# wiiceiver_v1.net
KiCad netlist of a schematic drawn in EAGLE
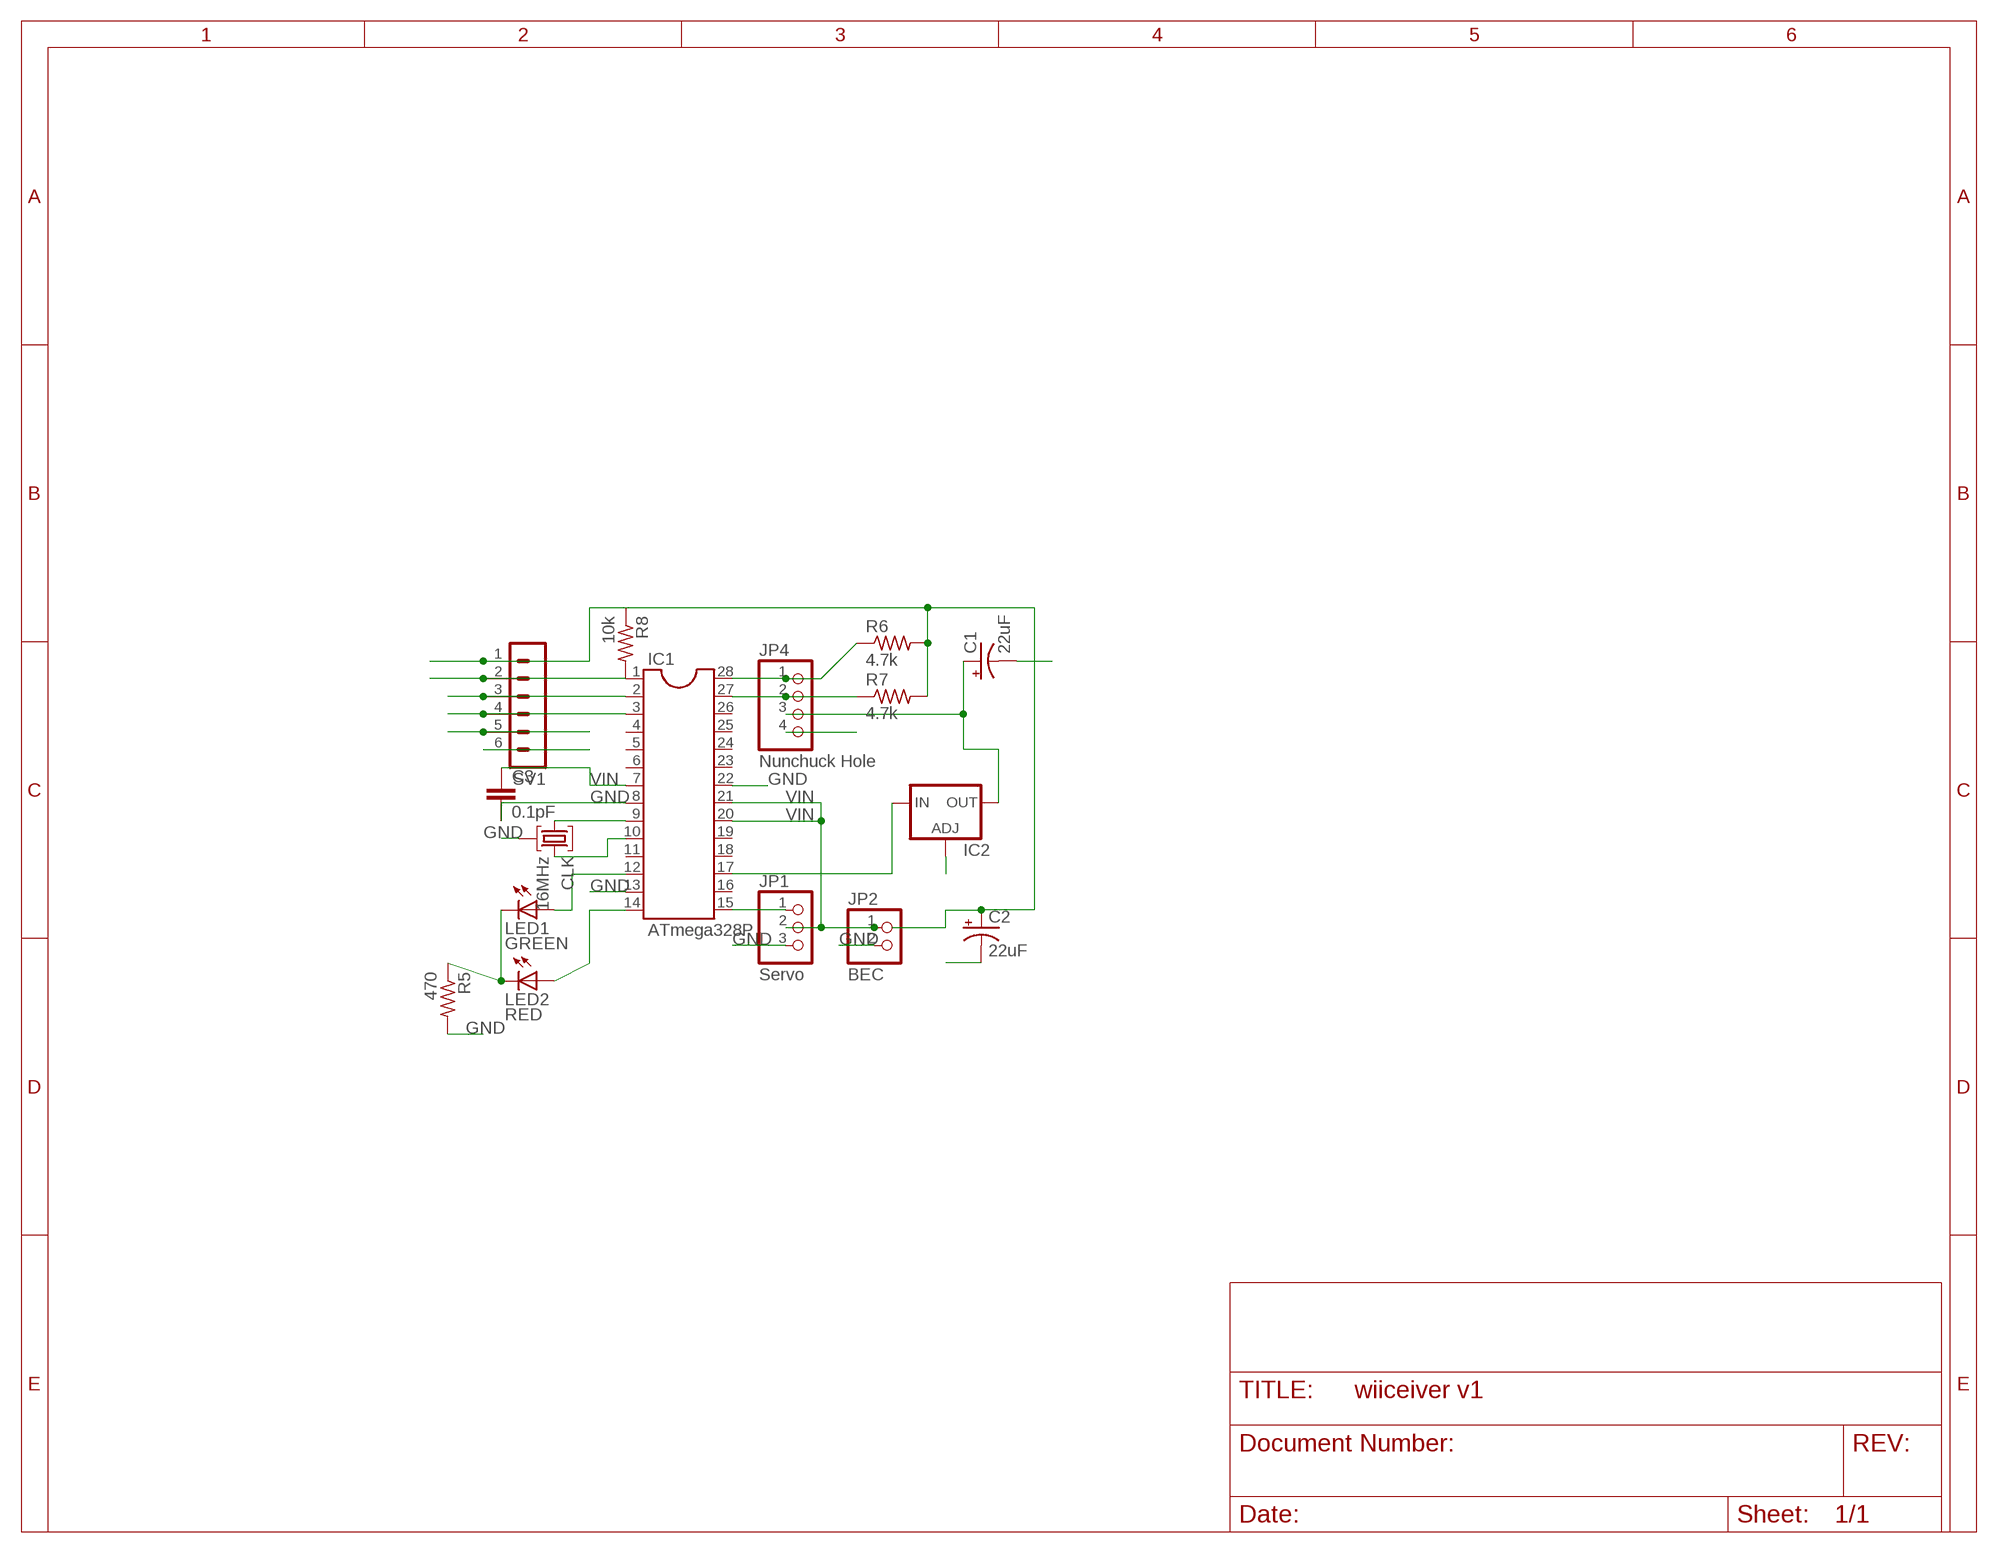
[diagram p0: schematic, sheet 1]

(export (version "E")
  (design (tool "Eeschema 10.0.6"))
  (components
    (comp (ref "C1")
      (value "22uF")
      (footprint "eagle-import:B45181A")
      (libsource (lib "eagle-import") (part "CPOL-USB45181A"))
    )
    (comp (ref "C2")
      (value "22uF")
      (footprint "eagle-import:B45181A")
      (libsource (lib "eagle-import") (part "CPOL-USB45181A"))
    )
    (comp (ref "C3")
      (value "0.1pF")
      (footprint "eagle-import:C5B2.5")
      (libsource (lib "eagle-import") (part "C5/2.5"))
    )
    (comp (ref "CLK")
      (value "16MHz")
      (footprint "eagle-import:HC49U")
      (libsource (lib "eagle-import") (part "IXFA"))
    )
    (comp (ref "IC1")
      (value "ATmega328P")
      (footprint "eagle-import:DIL28-3")
      (libsource (lib "eagle-import") (part "DIL28-3"))
    )
    (comp (ref "IC2")
      (value "LM317TS")
      (footprint "eagle-import:317TS")
      (libsource (lib "eagle-import") (part "LM317TS"))
    )
    (comp (ref "JP1")
      (value "Servo")
      (footprint "eagle-import:1X03")
      (libsource (lib "eagle-import") (part "PINHD-1X3"))
    )
    (comp (ref "JP2")
      (value "BEC")
      (footprint "eagle-import:1X02")
      (libsource (lib "eagle-import") (part "PINHD-1X2"))
    )
    (comp (ref "JP4")
      (value "Nunchuck Hole")
      (footprint "eagle-import:1X04")
      (libsource (lib "eagle-import") (part "PINHD-1X4"))
    )
    (comp (ref "LED1")
      (value "GREEN")
      (footprint "eagle-import:LED3MM")
      (libsource (lib "eagle-import") (part "LED3MM"))
    )
    (comp (ref "LED2")
      (value "RED")
      (footprint "eagle-import:LED3MM")
      (libsource (lib "eagle-import") (part "LED3MM"))
    )
    (comp (ref "R5")
      (value "470")
      (footprint "eagle-import:0204V")
      (libsource (lib "eagle-import") (part "R-US_0204/2V"))
    )
    (comp (ref "R6")
      (value "4.7k")
      (footprint "eagle-import:0204V")
      (libsource (lib "eagle-import") (part "R-US_0204/2V"))
    )
    (comp (ref "R7")
      (value "4.7k")
      (footprint "eagle-import:0204V")
      (libsource (lib "eagle-import") (part "R-US_0204/2V"))
    )
    (comp (ref "R8")
      (value "10k")
      (footprint "eagle-import:0204V")
      (libsource (lib "eagle-import") (part "R-US_0204/2V"))
    )
    (comp (ref "SV1")
      (value "MA06-1")
      (footprint "eagle-import:MA06-1")
      (libsource (lib "eagle-import") (part "MA06-1"))
    )
  )
  (nets
    (net (code "1") (name "/GND") (class "Default")
      (node (ref "C1") (pin "-") (pinfunction "-_-") (pintype "passive"))
      (node (ref "C2") (pin "-") (pinfunction "-_-") (pintype "passive"))
      (node (ref "C3") (pin "2") (pinfunction "2_2") (pintype "passive"))
      (node (ref "CLK") (pin "2") (pinfunction "2_2") (pintype "passive"))
      (node (ref "IC1") (pin "13") (pinfunction "13_13") (pintype "passive"))
      (node (ref "IC1") (pin "22") (pinfunction "22_22") (pintype "passive"))
      (node (ref "IC1") (pin "8") (pinfunction "8_8") (pintype "passive"))
      (node (ref "IC2") (pin "1") (pinfunction "ADJ_1") (pintype "input"))
      (node (ref "JP1") (pin "3") (pinfunction "3_3") (pintype "passive"))
      (node (ref "JP2") (pin "2") (pinfunction "2_2") (pintype "passive"))
      (node (ref "JP4") (pin "4") (pinfunction "4_4") (pintype "passive"))
      (node (ref "R5") (pin "2") (pinfunction "2_2") (pintype "passive"))
      (node (ref "SV1") (pin "5") (pinfunction "5_5") (pintype "passive"))
      (node (ref "SV1") (pin "6") (pinfunction "6_6") (pintype "passive"))
    )
    (net (code "2") (name "/VIN") (class "Default")
      (node (ref "C2") (pin "+") (pinfunction "+_+") (pintype "passive"))
      (node (ref "C3") (pin "1") (pinfunction "1_1") (pintype "passive"))
      (node (ref "IC1") (pin "20") (pinfunction "20_20") (pintype "passive"))
      (node (ref "IC1") (pin "21") (pinfunction "21_21") (pintype "passive"))
      (node (ref "IC1") (pin "7") (pinfunction "7_7") (pintype "passive"))
      (node (ref "JP1") (pin "2") (pinfunction "2_2") (pintype "passive"))
      (node (ref "JP2") (pin "1") (pinfunction "1_1") (pintype "passive"))
      (node (ref "R6") (pin "2") (pinfunction "2_2") (pintype "passive"))
      (node (ref "R7") (pin "2") (pinfunction "2_2") (pintype "passive"))
      (node (ref "R8") (pin "1") (pinfunction "1_1") (pintype "passive"))
      (node (ref "SV1") (pin "1") (pinfunction "1_1") (pintype "passive"))
    )
    (net (code "3") (name "Net-(CLK-Pad1)") (class "Default")
      (node (ref "CLK") (pin "1") (pinfunction "1_1") (pintype "passive"))
      (node (ref "IC1") (pin "9") (pinfunction "9_9") (pintype "passive"))
    )
    (net (code "4") (name "Net-(CLK-Pad3)") (class "Default")
      (node (ref "CLK") (pin "3") (pinfunction "3_3") (pintype "passive"))
      (node (ref "IC1") (pin "10") (pinfunction "10_10") (pintype "passive"))
    )
    (net (code "5") (name "Net-(IC1-Pad1)") (class "Default")
      (node (ref "IC1") (pin "1") (pinfunction "1_1") (pintype "passive"))
      (node (ref "R8") (pin "2") (pinfunction "2_2") (pintype "passive"))
      (node (ref "SV1") (pin "2") (pinfunction "2_2") (pintype "passive"))
    )
    (net (code "6") (name "Net-(IC1-Pad2)") (class "Default")
      (node (ref "IC1") (pin "2") (pinfunction "2_2") (pintype "passive"))
      (node (ref "SV1") (pin "3") (pinfunction "3_3") (pintype "passive"))
    )
    (net (code "7") (name "Net-(IC1-Pad3)") (class "Default")
      (node (ref "IC1") (pin "3") (pinfunction "3_3") (pintype "passive"))
      (node (ref "SV1") (pin "4") (pinfunction "4_4") (pintype "passive"))
    )
    (net (code "8") (name "Net-(IC1-Pad12)") (class "Default")
      (node (ref "IC1") (pin "12") (pinfunction "12_12") (pintype "passive"))
      (node (ref "LED1") (pin "A") (pinfunction "A_A") (pintype "passive"))
    )
    (net (code "9") (name "Net-(IC1-Pad14)") (class "Default")
      (node (ref "IC1") (pin "14") (pinfunction "14_14") (pintype "passive"))
      (node (ref "LED2") (pin "A") (pinfunction "A_A") (pintype "passive"))
    )
    (net (code "10") (name "Net-(IC1-Pad15)") (class "Default")
      (node (ref "IC1") (pin "15") (pinfunction "15_15") (pintype "passive"))
      (node (ref "JP1") (pin "1") (pinfunction "1_1") (pintype "passive"))
    )
    (net (code "11") (name "Net-(IC1-Pad27)") (class "Default")
      (node (ref "IC1") (pin "27") (pinfunction "27_27") (pintype "passive"))
      (node (ref "JP4") (pin "2") (pinfunction "2_2") (pintype "passive"))
      (node (ref "R7") (pin "1") (pinfunction "1_1") (pintype "passive"))
    )
    (net (code "12") (name "Net-(IC1-Pad28)") (class "Default")
      (node (ref "IC1") (pin "28") (pinfunction "28_28") (pintype "passive"))
      (node (ref "JP4") (pin "1") (pinfunction "1_1") (pintype "passive"))
      (node (ref "R6") (pin "1") (pinfunction "1_1") (pintype "passive"))
    )
    (net (code "13") (name "Net-(IC2-IN)") (class "Default")
      (node (ref "IC1") (pin "17") (pinfunction "17_17") (pintype "passive"))
      (node (ref "IC2") (pin "3") (pinfunction "IN_3") (pintype "input"))
    )
    (net (code "14") (name "Net-(IC2-OUT)") (class "Default")
      (node (ref "C1") (pin "+") (pinfunction "+_+") (pintype "passive"))
      (node (ref "IC2") (pin "2") (pinfunction "OUT_2") (pintype "passive"))
      (node (ref "JP4") (pin "3") (pinfunction "3_3") (pintype "passive"))
    )
    (net (code "15") (name "Net-(LED1-C)") (class "Default")
      (node (ref "LED1") (pin "K") (pinfunction "C_K") (pintype "passive"))
      (node (ref "LED2") (pin "K") (pinfunction "C_K") (pintype "passive"))
      (node (ref "R5") (pin "1") (pinfunction "1_1") (pintype "passive"))
    )
    (net (code "16") (name "unconnected-(IC1-Pad4)") (class "Default")
      (node (ref "IC1") (pin "4") (pinfunction "4_4") (pintype "passive"))
    )
    (net (code "17") (name "unconnected-(IC1-Pad5)") (class "Default")
      (node (ref "IC1") (pin "5") (pinfunction "5_5") (pintype "passive"))
    )
    (net (code "18") (name "unconnected-(IC1-Pad6)") (class "Default")
      (node (ref "IC1") (pin "6") (pinfunction "6_6") (pintype "passive"))
    )
    (net (code "19") (name "unconnected-(IC1-Pad11)") (class "Default")
      (node (ref "IC1") (pin "11") (pinfunction "11_11") (pintype "passive"))
    )
    (net (code "20") (name "unconnected-(IC1-Pad16)") (class "Default")
      (node (ref "IC1") (pin "16") (pinfunction "16_16") (pintype "passive"))
    )
    (net (code "21") (name "unconnected-(IC1-Pad18)") (class "Default")
      (node (ref "IC1") (pin "18") (pinfunction "18_18") (pintype "passive"))
    )
    (net (code "22") (name "unconnected-(IC1-Pad19)") (class "Default")
      (node (ref "IC1") (pin "19") (pinfunction "19_19") (pintype "passive"))
    )
    (net (code "23") (name "unconnected-(IC1-Pad23)") (class "Default")
      (node (ref "IC1") (pin "23") (pinfunction "23_23") (pintype "passive"))
    )
    (net (code "24") (name "unconnected-(IC1-Pad24)") (class "Default")
      (node (ref "IC1") (pin "24") (pinfunction "24_24") (pintype "passive"))
    )
    (net (code "25") (name "unconnected-(IC1-Pad25)") (class "Default")
      (node (ref "IC1") (pin "25") (pinfunction "25_25") (pintype "passive"))
    )
    (net (code "26") (name "unconnected-(IC1-Pad26)") (class "Default")
      (node (ref "IC1") (pin "26") (pinfunction "26_26") (pintype "passive"))
    )
  )
)
